# ACNode.net
KiCad netlist of a schematic drawn in EAGLE
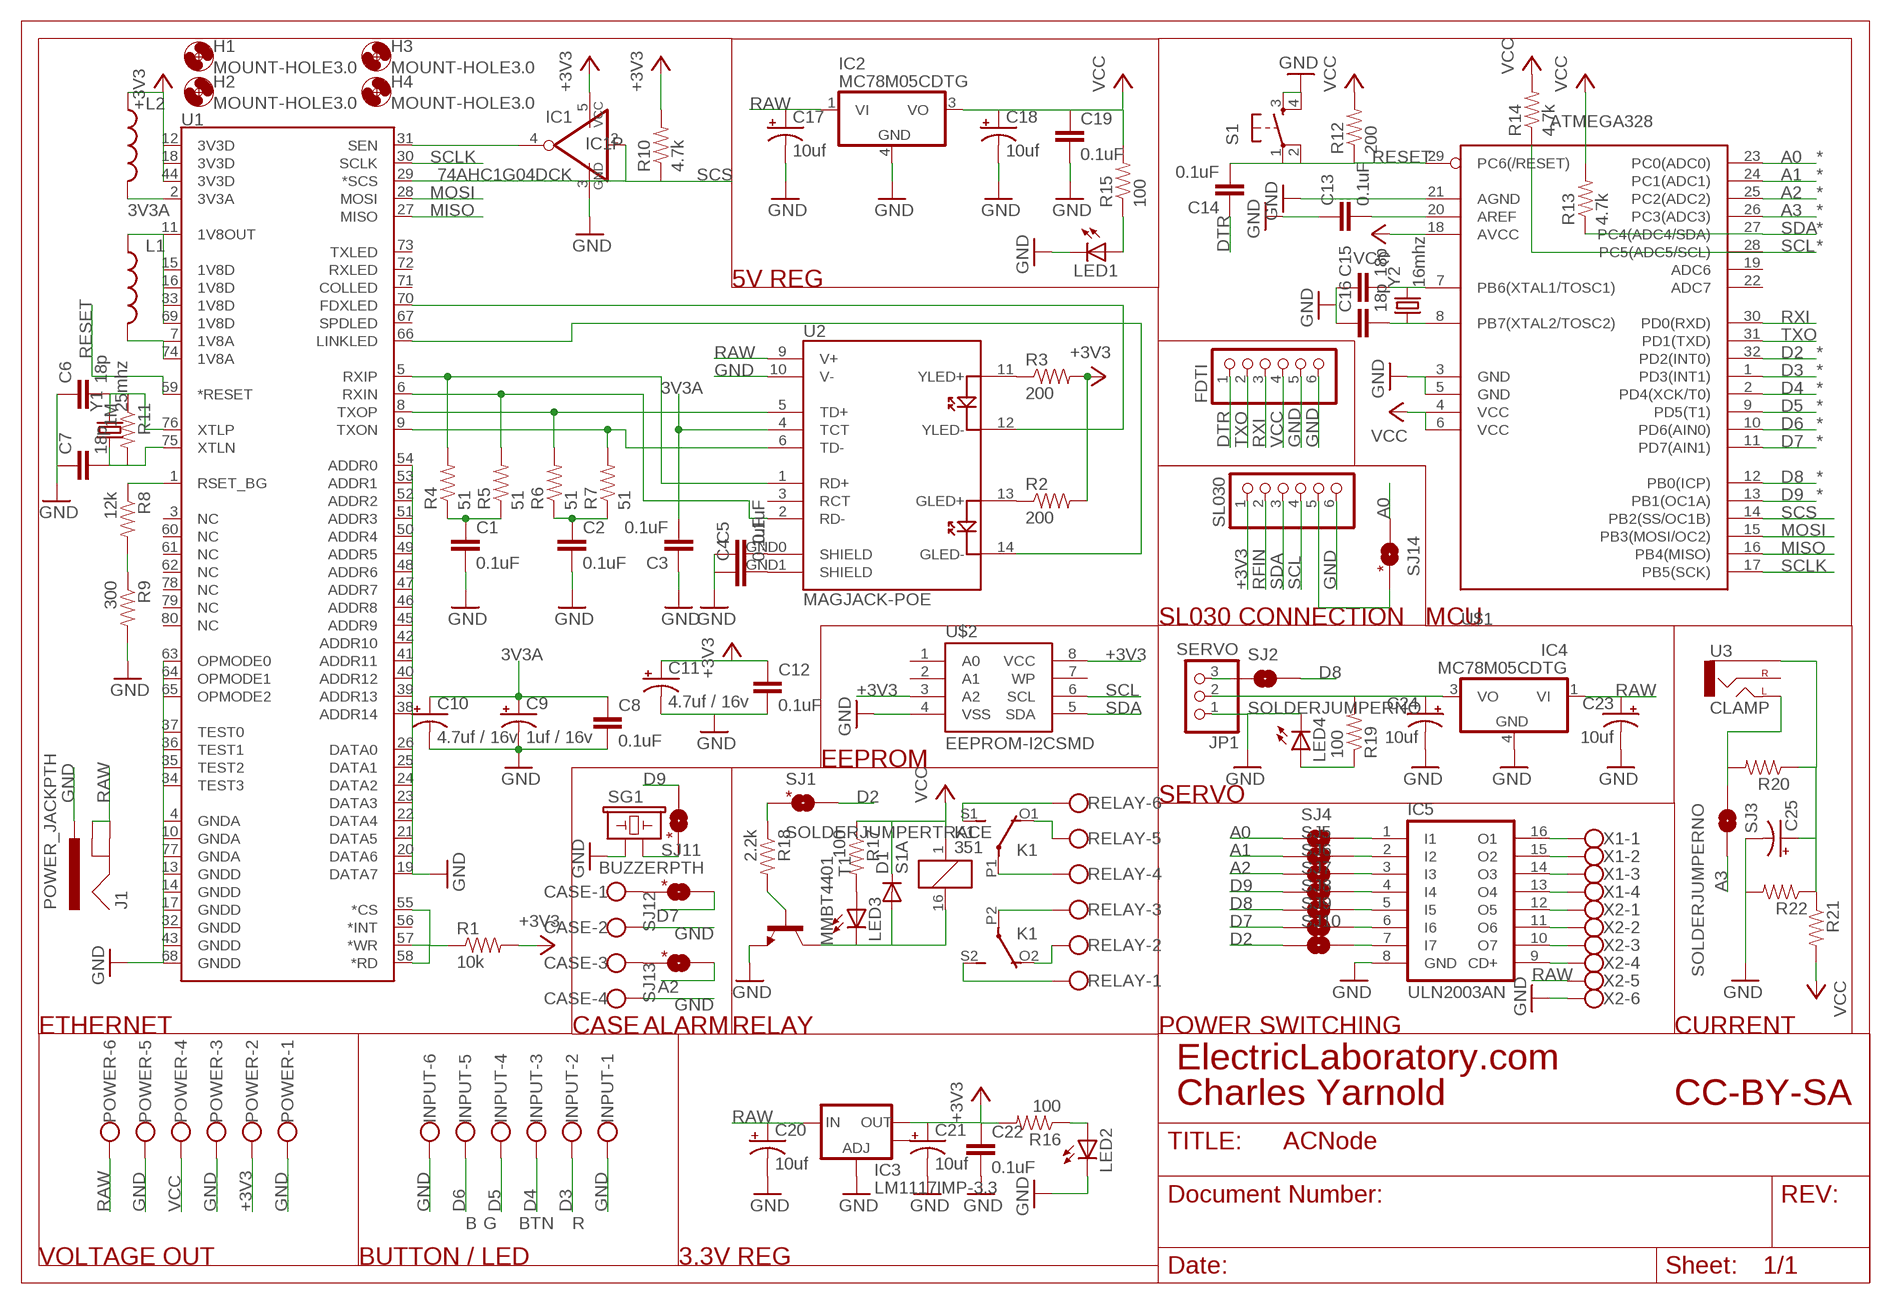
[diagram p0: schematic, sheet 1]

(export (version "E")
  (design (tool "Eeschema 10.0.6"))
  (components
    (comp (ref "C1")
      (value "0.1uF")
      (footprint "eagle-import:0603-CAP")
      (libsource (lib "eagle-import") (part "CAP0603-CAP"))
    )
    (comp (ref "C2")
      (value "0.1uF")
      (footprint "eagle-import:0603-CAP")
      (libsource (lib "eagle-import") (part "CAP0603-CAP"))
    )
    (comp (ref "C3")
      (value "0.1uF")
      (footprint "eagle-import:0603-CAP")
      (libsource (lib "eagle-import") (part "CAP0603-CAP"))
    )
    (comp (ref "C4")
      (value "0.1uF")
      (footprint "eagle-import:0603-CAP")
      (libsource (lib "eagle-import") (part "CAP0603-CAP"))
    )
    (comp (ref "C5")
      (value "0.1uF")
      (footprint "eagle-import:0603-CAP")
      (libsource (lib "eagle-import") (part "CAP0603-CAP"))
    )
    (comp (ref "C6")
      (value "18p")
      (footprint "eagle-import:0603-CAP")
      (libsource (lib "eagle-import") (part "CAP0603-CAP"))
    )
    (comp (ref "C7")
      (value "18p")
      (footprint "eagle-import:0603-CAP")
      (libsource (lib "eagle-import") (part "CAP0603-CAP"))
    )
    (comp (ref "C8")
      (value "0.1uF")
      (footprint "eagle-import:0603-CAP")
      (libsource (lib "eagle-import") (part "CAP0603-CAP"))
    )
    (comp (ref "C9")
      (value "1uf / 16v")
      (footprint "eagle-import:EIA3216")
      (libsource (lib "eagle-import") (part "CAP_POL1206"))
    )
    (comp (ref "C10")
      (value "4.7uf / 16v")
      (footprint "eagle-import:EIA3216")
      (libsource (lib "eagle-import") (part "CAP_POL1206"))
    )
    (comp (ref "C11")
      (value "4.7uf / 16v")
      (footprint "eagle-import:EIA3216")
      (libsource (lib "eagle-import") (part "CAP_POL1206"))
    )
    (comp (ref "C12")
      (value "0.1uF")
      (footprint "eagle-import:0603-CAP")
      (libsource (lib "eagle-import") (part "CAP0603-CAP"))
    )
    (comp (ref "C13")
      (value "0.1uF")
      (footprint "eagle-import:0603-CAP")
      (libsource (lib "eagle-import") (part "CAP0603-CAP"))
    )
    (comp (ref "C14")
      (value "0.1uF")
      (footprint "eagle-import:0603-CAP")
      (libsource (lib "eagle-import") (part "CAP0603-CAP"))
    )
    (comp (ref "C15")
      (value "18p")
      (footprint "eagle-import:0603-CAP")
      (libsource (lib "eagle-import") (part "CAP0603-CAP"))
    )
    (comp (ref "C16")
      (value "18p")
      (footprint "eagle-import:0603-CAP")
      (libsource (lib "eagle-import") (part "CAP0603-CAP"))
    )
    (comp (ref "C17")
      (value "10uf")
      (footprint "eagle-import:EIA3216")
      (libsource (lib "eagle-import") (part "CAP_POL1206"))
    )
    (comp (ref "C18")
      (value "10uf")
      (footprint "eagle-import:EIA3216")
      (libsource (lib "eagle-import") (part "CAP_POL1206"))
    )
    (comp (ref "C19")
      (value "0.1uF")
      (footprint "eagle-import:0603-CAP")
      (libsource (lib "eagle-import") (part "CAP0603-CAP"))
    )
    (comp (ref "C20")
      (value "10uf")
      (footprint "eagle-import:EIA3216")
      (libsource (lib "eagle-import") (part "CAP_POL1206"))
    )
    (comp (ref "C21")
      (value "10uf")
      (footprint "eagle-import:EIA3216")
      (libsource (lib "eagle-import") (part "CAP_POL1206"))
    )
    (comp (ref "C22")
      (value "0.1uF")
      (footprint "eagle-import:0603-CAP")
      (libsource (lib "eagle-import") (part "CAP0603-CAP"))
    )
    (comp (ref "C23")
      (value "10uf")
      (footprint "eagle-import:EIA3216")
      (libsource (lib "eagle-import") (part "CAP_POL1206"))
    )
    (comp (ref "C24")
      (value "10uf")
      (footprint "eagle-import:EIA3216")
      (libsource (lib "eagle-import") (part "CAP_POL1206"))
    )
    (comp (ref "C25")
      (value "CAP_POL1206")
      (footprint "eagle-import:EIA3216")
      (libsource (lib "eagle-import") (part "CAP_POL1206"))
    )
    (comp (ref "CASE")
      (value "W237-4")
      (footprint "eagle-import:W237-4")
      (libsource (lib "eagle-import") (part "W237-4"))
    )
    (comp (ref "D1")
      (value "S1A")
      (footprint "eagle-import:DO-214AC")
      (libsource (lib "eagle-import") (part "DIODE-DO-214AC"))
    )
    (comp (ref "FDTI")
      (value "PINHD-1X6")
      (footprint "eagle-import:1X06")
      (libsource (lib "eagle-import") (part "PINHD-1X6"))
    )
    (comp (ref "H1")
      (value "MOUNT-HOLE3.0")
      (footprint "eagle-import:3,0")
      (libsource (lib "eagle-import") (part "MOUNT-HOLE3.0"))
    )
    (comp (ref "H2")
      (value "MOUNT-HOLE3.0")
      (footprint "eagle-import:3,0")
      (libsource (lib "eagle-import") (part "MOUNT-HOLE3.0"))
    )
    (comp (ref "H3")
      (value "MOUNT-HOLE3.0")
      (footprint "eagle-import:3,0")
      (libsource (lib "eagle-import") (part "MOUNT-HOLE3.0"))
    )
    (comp (ref "H4")
      (value "MOUNT-HOLE3.0")
      (footprint "eagle-import:3,0")
      (libsource (lib "eagle-import") (part "MOUNT-HOLE3.0"))
    )
    (comp (ref "IC1")
      (value "74AHC1G04DCK")
      (footprint "eagle-import:SC70-5")
      (libsource (lib "eagle-import") (part "741G04DCKAHC"))
    )
    (comp (ref "IC2")
      (value "MC78M05CDTG")
      (footprint "eagle-import:DPACK_3")
      (libsource (lib "eagle-import") (part "MC78M05CDTG"))
    )
    (comp (ref "IC3")
      (value "LM1117IMP-3.3")
      (footprint "eagle-import:SOT223")
      (libsource (lib "eagle-import") (part "V_REG_LM1117SOT223"))
    )
    (comp (ref "IC4")
      (value "MC78M05CDTG")
      (footprint "eagle-import:DPACK_3")
      (libsource (lib "eagle-import") (part "MC78M05CDTG"))
    )
    (comp (ref "IC5")
      (value "ULN2003AN")
      (footprint "eagle-import:DIL16")
      (libsource (lib "eagle-import") (part "ULN2003AN"))
    )
    (comp (ref "INPUT")
      (value "W237-6")
      (footprint "eagle-import:W237-6")
      (libsource (lib "eagle-import") (part "W237-6"))
    )
    (comp (ref "J1")
      (value "POWER_JACKPTH")
      (footprint "eagle-import:POWER_JACK_PTH")
      (libsource (lib "eagle-import") (part "POWER_JACKPTH"))
    )
    (comp (ref "JP1")
      (value "SERVO")
      (footprint "eagle-import:1X03")
      (libsource (lib "eagle-import") (part "PINHD-1X3"))
    )
    (comp (ref "K1")
      (value "351")
      (footprint "eagle-import:351")
      (libsource (lib "eagle-import") (part "351"))
    )
    (comp (ref "L1")
      (value "INDUCTOR1206H*")
      (footprint "eagle-import:INDUCTOR-1206")
      (libsource (lib "eagle-import") (part "INDUCTORH1206"))
    )
    (comp (ref "L2")
      (value "INDUCTOR1206H*")
      (footprint "eagle-import:INDUCTOR-1206")
      (libsource (lib "eagle-import") (part "INDUCTORH1206"))
    )
    (comp (ref "LED1")
      (value "LED0603")
      (footprint "eagle-import:LED-0603")
      (libsource (lib "eagle-import") (part "LED0603"))
    )
    (comp (ref "LED2")
      (value "LED0603")
      (footprint "eagle-import:LED-0603")
      (libsource (lib "eagle-import") (part "LED0603"))
    )
    (comp (ref "LED3")
      (value "LED0603")
      (footprint "eagle-import:LED-0603")
      (libsource (lib "eagle-import") (part "LED0603"))
    )
    (comp (ref "LED4")
      (value "LED0603")
      (footprint "eagle-import:LED-0603")
      (libsource (lib "eagle-import") (part "LED0603"))
    )
    (comp (ref "POWER")
      (value "W237-6")
      (footprint "eagle-import:W237-6")
      (libsource (lib "eagle-import") (part "W237-6"))
    )
    (comp (ref "R1")
      (value "10k")
      (footprint "eagle-import:0603-RES")
      (libsource (lib "eagle-import") (part "RESISTOR0603-RES"))
    )
    (comp (ref "R2")
      (value "200")
      (footprint "eagle-import:0603-RES")
      (libsource (lib "eagle-import") (part "RESISTOR0603-RES"))
    )
    (comp (ref "R3")
      (value "200")
      (footprint "eagle-import:0603-RES")
      (libsource (lib "eagle-import") (part "RESISTOR0603-RES"))
    )
    (comp (ref "R4")
      (value "51")
      (footprint "eagle-import:0603-RES")
      (libsource (lib "eagle-import") (part "RESISTOR0603-RES"))
    )
    (comp (ref "R5")
      (value "51")
      (footprint "eagle-import:0603-RES")
      (libsource (lib "eagle-import") (part "RESISTOR0603-RES"))
    )
    (comp (ref "R6")
      (value "51")
      (footprint "eagle-import:0603-RES")
      (libsource (lib "eagle-import") (part "RESISTOR0603-RES"))
    )
    (comp (ref "R7")
      (value "51")
      (footprint "eagle-import:0603-RES")
      (libsource (lib "eagle-import") (part "RESISTOR0603-RES"))
    )
    (comp (ref "R8")
      (value "12k")
      (footprint "eagle-import:0603-RES")
      (libsource (lib "eagle-import") (part "RESISTOR0603-RES"))
    )
    (comp (ref "R9")
      (value "300")
      (footprint "eagle-import:0603-RES")
      (libsource (lib "eagle-import") (part "RESISTOR0603-RES"))
    )
    (comp (ref "R10")
      (value "4.7k")
      (footprint "eagle-import:0603-RES")
      (libsource (lib "eagle-import") (part "RESISTOR0603-RES"))
    )
    (comp (ref "R11")
      (value "1M")
      (footprint "eagle-import:0603-RES")
      (libsource (lib "eagle-import") (part "RESISTOR0603-RES"))
    )
    (comp (ref "R12")
      (value "200")
      (footprint "eagle-import:0603-RES")
      (libsource (lib "eagle-import") (part "RESISTOR0603-RES"))
    )
    (comp (ref "R13")
      (value "4.7k")
      (footprint "eagle-import:0603-RES")
      (libsource (lib "eagle-import") (part "RESISTOR0603-RES"))
    )
    (comp (ref "R14")
      (value "4.7k")
      (footprint "eagle-import:0603-RES")
      (libsource (lib "eagle-import") (part "RESISTOR0603-RES"))
    )
    (comp (ref "R15")
      (value "100")
      (footprint "eagle-import:0603-RES")
      (libsource (lib "eagle-import") (part "RESISTOR0603-RES"))
    )
    (comp (ref "R16")
      (value "100")
      (footprint "eagle-import:0603-RES")
      (libsource (lib "eagle-import") (part "RESISTOR0603-RES"))
    )
    (comp (ref "R17")
      (value "100")
      (footprint "eagle-import:0603-RES")
      (libsource (lib "eagle-import") (part "RESISTOR0603-RES"))
    )
    (comp (ref "R18")
      (value "2.2k")
      (footprint "eagle-import:0603-RES")
      (libsource (lib "eagle-import") (part "RESISTOR0603-RES"))
    )
    (comp (ref "R19")
      (value "100")
      (footprint "eagle-import:0603-RES")
      (libsource (lib "eagle-import") (part "RESISTOR0603-RES"))
    )
    (comp (ref "R20")
      (value "RESISTOR0603-RES")
      (footprint "eagle-import:0603-RES")
      (libsource (lib "eagle-import") (part "RESISTOR0603-RES"))
    )
    (comp (ref "R21")
      (value "RESISTOR0603-RES")
      (footprint "eagle-import:0603-RES")
      (libsource (lib "eagle-import") (part "RESISTOR0603-RES"))
    )
    (comp (ref "R22")
      (value "RESISTOR0603-RES")
      (footprint "eagle-import:0603-RES")
      (libsource (lib "eagle-import") (part "RESISTOR0603-RES"))
    )
    (comp (ref "RELAY")
      (value "W237-6")
      (footprint "eagle-import:W237-6")
      (libsource (lib "eagle-import") (part "W237-6"))
    )
    (comp (ref "S1")
      (value "TAC_SWITCHSMD")
      (footprint "eagle-import:TACTILE_SWITCH_SMD")
      (libsource (lib "eagle-import") (part "TAC_SWITCHSMD"))
    )
    (comp (ref "SG1")
      (value "BUZZERPTH")
      (footprint "eagle-import:BUZZER-12MM")
      (libsource (lib "eagle-import") (part "BUZZERPTH"))
    )
    (comp (ref "SJ1")
      (value "SOLDERJUMPERTRACE")
      (footprint "eagle-import:SJ_2S-TRACE")
      (libsource (lib "eagle-import") (part "SOLDERJUMPERTRACE"))
    )
    (comp (ref "SJ2")
      (value "SOLDERJUMPERNO")
      (footprint "eagle-import:SJ_2S-NO")
      (libsource (lib "eagle-import") (part "SOLDERJUMPERNO"))
    )
    (comp (ref "SJ3")
      (value "SOLDERJUMPERNO")
      (footprint "eagle-import:SJ_2S-NO")
      (libsource (lib "eagle-import") (part "SOLDERJUMPERNO"))
    )
    (comp (ref "SJ4")
      (value "SOLDERJUMPERNO")
      (footprint "eagle-import:SJ_2S-NO")
      (libsource (lib "eagle-import") (part "SOLDERJUMPERNO"))
    )
    (comp (ref "SJ5")
      (value "SOLDERJUMPERNO")
      (footprint "eagle-import:SJ_2S-NO")
      (libsource (lib "eagle-import") (part "SOLDERJUMPERNO"))
    )
    (comp (ref "SJ6")
      (value "SOLDERJUMPERNO")
      (footprint "eagle-import:SJ_2S-NO")
      (libsource (lib "eagle-import") (part "SOLDERJUMPERNO"))
    )
    (comp (ref "SJ7")
      (value "SOLDERJUMPERNO")
      (footprint "eagle-import:SJ_2S-NO")
      (libsource (lib "eagle-import") (part "SOLDERJUMPERNO"))
    )
    (comp (ref "SJ8")
      (value "SOLDERJUMPERNO")
      (footprint "eagle-import:SJ_2S-NO")
      (libsource (lib "eagle-import") (part "SOLDERJUMPERNO"))
    )
    (comp (ref "SJ9")
      (value "SOLDERJUMPERNO")
      (footprint "eagle-import:SJ_2S-NO")
      (libsource (lib "eagle-import") (part "SOLDERJUMPERNO"))
    )
    (comp (ref "SJ10")
      (value "SOLDERJUMPERNO")
      (footprint "eagle-import:SJ_2S-NO")
      (libsource (lib "eagle-import") (part "SOLDERJUMPERNO"))
    )
    (comp (ref "SJ11")
      (value "SOLDERJUMPERTRACE")
      (footprint "eagle-import:SJ_2S-TRACE")
      (libsource (lib "eagle-import") (part "SOLDERJUMPERTRACE"))
    )
    (comp (ref "SJ12")
      (value "SOLDERJUMPERTRACE")
      (footprint "eagle-import:SJ_2S-TRACE")
      (libsource (lib "eagle-import") (part "SOLDERJUMPERTRACE"))
    )
    (comp (ref "SJ13")
      (value "SOLDERJUMPERTRACE")
      (footprint "eagle-import:SJ_2S-TRACE")
      (libsource (lib "eagle-import") (part "SOLDERJUMPERTRACE"))
    )
    (comp (ref "SJ14")
      (value "SOLDERJUMPERTRACE")
      (footprint "eagle-import:SJ_2S-TRACE")
      (libsource (lib "eagle-import") (part "SOLDERJUMPERTRACE"))
    )
    (comp (ref "SL030")
      (value "PINHD-1X6")
      (footprint "eagle-import:1X06")
      (libsource (lib "eagle-import") (part "PINHD-1X6"))
    )
    (comp (ref "T1")
      (value "MMBT4401")
      (footprint "eagle-import:SOT23-BEC")
      (libsource (lib "eagle-import") (part "-NPN-SOT23-BECMMBT4401LT1"))
    )
    (comp (ref "U$1")
      (value "ATMEGA328")
      (footprint "eagle-import:TQFP32-08")
      (libsource (lib "eagle-import") (part "AVR-MEGA8-AI"))
    )
    (comp (ref "U$2")
      (value "EEPROM-I2CSMD")
      (footprint "eagle-import:SO08")
      (libsource (lib "eagle-import") (part "EEPROM-I2CSMD"))
    )
    (comp (ref "U1")
      (value "W5100")
      (footprint "eagle-import:LQFP-80")
      (libsource (lib "eagle-import") (part "W5100"))
    )
    (comp (ref "U2")
      (value "MAGJACK-POE")
      (footprint "eagle-import:MAGJACK-POE")
      (libsource (lib "eagle-import") (part "MAGJACK-POE"))
    )
    (comp (ref "U3")
      (value "CLAMP")
      (footprint "eagle-import:AUDIO-JACK")
      (libsource (lib "eagle-import") (part "AUDIO-JACKPTH"))
    )
    (comp (ref "X1")
      (value "W237-4")
      (footprint "eagle-import:W237-4")
      (libsource (lib "eagle-import") (part "W237-4"))
    )
    (comp (ref "X2")
      (value "W237-6")
      (footprint "eagle-import:W237-6")
      (libsource (lib "eagle-import") (part "W237-6"))
    )
    (comp (ref "Y1")
      (value "25mhz")
      (footprint "eagle-import:HC49UP")
      (libsource (lib "eagle-import") (part "CRYSTALSMD"))
    )
    (comp (ref "Y2")
      (value "16mhz")
      (footprint "eagle-import:HC49UP")
      (libsource (lib "eagle-import") (part "CRYSTALSMD"))
    )
  )
  (nets
    (net (code "1") (name "+3V3") (class "Default")
      (node (ref "C11") (pin "A") (pinfunction "+_A") (pintype "passive"))
      (node (ref "C12") (pin "1") (pinfunction "1_1") (pintype "passive"))
      (node (ref "C21") (pin "A") (pinfunction "+_A") (pintype "passive"))
      (node (ref "C22") (pin "1") (pinfunction "1_1") (pintype "passive"))
      (node (ref "IC1") (pin "5") (pinfunction "VCC_5") (pintype "power_in"))
      (node (ref "IC3") (pin "2") (pinfunction "OUT_2") (pintype "output"))
      (node (ref "L2") (pin "P$1") (pinfunction "1_P$1") (pintype "passive"))
      (node (ref "POWER") (pin "2") (pinfunction "KL_2") (pintype "passive"))
      (node (ref "R1") (pin "2") (pinfunction "2_2") (pintype "passive"))
      (node (ref "R10") (pin "2") (pinfunction "2_2") (pintype "passive"))
      (node (ref "R16") (pin "2") (pinfunction "2_2") (pintype "passive"))
      (node (ref "R2") (pin "2") (pinfunction "2_2") (pintype "passive"))
      (node (ref "R3") (pin "2") (pinfunction "2_2") (pintype "passive"))
      (node (ref "SL030") (pin "1") (pinfunction "1_1") (pintype "passive"))
      (node (ref "U$2") (pin "3") (pinfunction "A2_3") (pintype "bidirectional"))
      (node (ref "U$2") (pin "8") (pinfunction "VCC_8") (pintype "power_in"))
      (node (ref "U1") (pin "12") (pinfunction "3V3D_12") (pintype "bidirectional"))
      (node (ref "U1") (pin "18") (pinfunction "3V3D_18") (pintype "bidirectional"))
      (node (ref "U1") (pin "44") (pinfunction "3V3D_44") (pintype "bidirectional"))
    )
    (net (code "2") (name "/3V3A") (class "Default")
      (node (ref "C10") (pin "A") (pinfunction "+_A") (pintype "passive"))
      (node (ref "C3") (pin "2") (pinfunction "2_2") (pintype "passive"))
      (node (ref "C8") (pin "1") (pinfunction "1_1") (pintype "passive"))
      (node (ref "C9") (pin "A") (pinfunction "+_A") (pintype "passive"))
      (node (ref "L2") (pin "P$2") (pinfunction "2_P$2") (pintype "passive"))
      (node (ref "U1") (pin "2") (pinfunction "3V3A_2") (pintype "bidirectional"))
      (node (ref "U2") (pin "4") (pinfunction "TCT_4") (pintype "bidirectional"))
    )
    (net (code "3") (name "/A0") (class "Default")
      (node (ref "SJ14") (pin "1") (pinfunction "1_1") (pintype "passive"))
      (node (ref "SJ4") (pin "1") (pinfunction "1_1") (pintype "passive"))
      (node (ref "U$1") (pin "23") (pinfunction "PC0(ADC0)_23") (pintype "bidirectional"))
    )
    (net (code "4") (name "/A1") (class "Default")
      (node (ref "SJ5") (pin "1") (pinfunction "1_1") (pintype "passive"))
      (node (ref "U$1") (pin "24") (pinfunction "PC1(ADC1)_24") (pintype "bidirectional"))
    )
    (net (code "5") (name "/A2") (class "Default")
      (node (ref "SJ13") (pin "2") (pinfunction "2_2") (pintype "passive"))
      (node (ref "SJ6") (pin "1") (pinfunction "1_1") (pintype "passive"))
      (node (ref "U$1") (pin "25") (pinfunction "PC2(ADC2)_25") (pintype "bidirectional"))
    )
    (net (code "6") (name "/A3") (class "Default")
      (node (ref "SJ3") (pin "2") (pinfunction "2_2") (pintype "passive"))
      (node (ref "U$1") (pin "26") (pinfunction "PC3(ADC3)_26") (pintype "bidirectional"))
    )
    (net (code "7") (name "/D2") (class "Default")
      (node (ref "SJ1") (pin "2") (pinfunction "2_2") (pintype "passive"))
      (node (ref "SJ10") (pin "1") (pinfunction "1_1") (pintype "passive"))
      (node (ref "U$1") (pin "32") (pinfunction "PD2(INT0)_32") (pintype "bidirectional"))
    )
    (net (code "8") (name "/D3") (class "Default")
      (node (ref "INPUT") (pin "2") (pinfunction "KL_2") (pintype "passive"))
      (node (ref "U$1") (pin "1") (pinfunction "PD3(INT1)_1") (pintype "bidirectional"))
    )
    (net (code "9") (name "/D4") (class "Default")
      (node (ref "INPUT") (pin "3") (pinfunction "KL_3") (pintype "passive"))
      (node (ref "U$1") (pin "2") (pinfunction "PD4(XCK/T0)_2") (pintype "bidirectional"))
    )
    (net (code "10") (name "/D5") (class "Default")
      (node (ref "INPUT") (pin "4") (pinfunction "KL_4") (pintype "passive"))
      (node (ref "U$1") (pin "9") (pinfunction "PD5(T1)_9") (pintype "bidirectional"))
    )
    (net (code "11") (name "/D6") (class "Default")
      (node (ref "INPUT") (pin "5") (pinfunction "KL_5") (pintype "passive"))
      (node (ref "U$1") (pin "10") (pinfunction "PD6(AIN0)_10") (pintype "bidirectional"))
    )
    (net (code "12") (name "/D7") (class "Default")
      (node (ref "SJ12") (pin "2") (pinfunction "2_2") (pintype "passive"))
      (node (ref "SJ9") (pin "1") (pinfunction "1_1") (pintype "passive"))
      (node (ref "U$1") (pin "11") (pinfunction "PD7(AIN1)_11") (pintype "bidirectional"))
    )
    (net (code "13") (name "/D8") (class "Default")
      (node (ref "SJ2") (pin "2") (pinfunction "2_2") (pintype "passive"))
      (node (ref "SJ8") (pin "1") (pinfunction "1_1") (pintype "passive"))
      (node (ref "U$1") (pin "12") (pinfunction "PB0(ICP)_12") (pintype "bidirectional"))
    )
    (net (code "14") (name "/D9") (class "Default")
      (node (ref "SJ11") (pin "2") (pinfunction "2_2") (pintype "passive"))
      (node (ref "SJ7") (pin "1") (pinfunction "1_1") (pintype "passive"))
      (node (ref "U$1") (pin "13") (pinfunction "PB1(OC1A)_13") (pintype "bidirectional"))
    )
    (net (code "15") (name "/DTR") (class "Default")
      (node (ref "C14") (pin "1") (pinfunction "1_1") (pintype "passive"))
      (node (ref "FDTI") (pin "1") (pinfunction "1_1") (pintype "passive"))
    )
    (net (code "16") (name "/MISO") (class "Default")
      (node (ref "U$1") (pin "16") (pinfunction "PB4(MISO)_16") (pintype "bidirectional"))
      (node (ref "U1") (pin "27") (pinfunction "MISO_27") (pintype "bidirectional"))
    )
    (net (code "17") (name "/MOSI") (class "Default")
      (node (ref "U$1") (pin "15") (pinfunction "PB3(MOSI/OC2)_15") (pintype "bidirectional"))
      (node (ref "U1") (pin "28") (pinfunction "MOSI_28") (pintype "bidirectional"))
    )
    (net (code "18") (name "/RAW") (class "Default")
      (node (ref "C17") (pin "A") (pinfunction "+_A") (pintype "passive"))
      (node (ref "C20") (pin "A") (pinfunction "+_A") (pintype "passive"))
      (node (ref "C23") (pin "A") (pinfunction "+_A") (pintype "passive"))
      (node (ref "IC2") (pin "1") (pinfunction "VI_1") (pintype "input"))
      (node (ref "IC3") (pin "3") (pinfunction "IN_3") (pintype "input"))
      (node (ref "IC4") (pin "1") (pinfunction "VI_1") (pintype "input"))
      (node (ref "J1") (pin "GND") (pinfunction "GND_GND") (pintype "bidirectional"))
      (node (ref "J1") (pin "GNDBREAK") (pinfunction "GNDBREAK_GNDBREAK") (pintype "bidirectional"))
      (node (ref "POWER") (pin "6") (pinfunction "KL_6") (pintype "passive"))
      (node (ref "U2") (pin "9") (pinfunction "V+_9") (pintype "bidirectional"))
      (node (ref "X2") (pin "5") (pinfunction "KL_5") (pintype "passive"))
    )
    (net (code "19") (name "/RESET") (class "Default")
      (node (ref "C14") (pin "2") (pinfunction "2_2") (pintype "passive"))
      (node (ref "R12") (pin "1") (pinfunction "1_1") (pintype "passive"))
      (node (ref "S1") (pin "1") (pinfunction "1_1") (pintype "passive"))
      (node (ref "S1") (pin "2") (pinfunction "2_2") (pintype "passive"))
      (node (ref "U$1") (pin "29") (pinfunction "PC6(/RESET)_29") (pintype "bidirectional"))
      (node (ref "U1") (pin "59") (pinfunction "*RESET_59") (pintype "bidirectional"))
    )
    (net (code "20") (name "/RFIN") (class "Default")
      (node (ref "SL030") (pin "2") (pinfunction "2_2") (pintype "passive"))
    )
    (net (code "21") (name "/RXI") (class "Default")
      (node (ref "FDTI") (pin "3") (pinfunction "3_3") (pintype "passive"))
      (node (ref "U$1") (pin "30") (pinfunction "PD0(RXD)_30") (pintype "bidirectional"))
    )
    (net (code "22") (name "/SCL") (class "Default")
      (node (ref "R14") (pin "1") (pinfunction "1_1") (pintype "passive"))
      (node (ref "SL030") (pin "4") (pinfunction "4_4") (pintype "passive"))
      (node (ref "U$1") (pin "28") (pinfunction "PC5(ADC5/SCL)_28") (pintype "bidirectional"))
      (node (ref "U$2") (pin "6") (pinfunction "SCL_6") (pintype "bidirectional"))
    )
    (net (code "23") (name "/SCLK") (class "Default")
      (node (ref "U$1") (pin "17") (pinfunction "PB5(SCK)_17") (pintype "bidirectional"))
      (node (ref "U1") (pin "30") (pinfunction "SCLK_30") (pintype "bidirectional"))
    )
    (net (code "24") (name "/SCS") (class "Default")
      (node (ref "IC1") (pin "2") (pinfunction "I_2") (pintype "input"))
      (node (ref "R10") (pin "1") (pinfunction "1_1") (pintype "passive"))
      (node (ref "U$1") (pin "14") (pinfunction "PB2(SS/OC1B)_14") (pintype "bidirectional"))
      (node (ref "U1") (pin "29") (pinfunction "*SCS_29") (pintype "bidirectional"))
    )
    (net (code "25") (name "/SDA") (class "Default")
      (node (ref "R13") (pin "1") (pinfunction "1_1") (pintype "passive"))
      (node (ref "SL030") (pin "3") (pinfunction "3_3") (pintype "passive"))
      (node (ref "U$1") (pin "27") (pinfunction "PC4(ADC4/SDA)_27") (pintype "bidirectional"))
      (node (ref "U$2") (pin "5") (pinfunction "SDA_5") (pintype "bidirectional"))
    )
    (net (code "26") (name "/TXO") (class "Default")
      (node (ref "FDTI") (pin "2") (pinfunction "2_2") (pintype "passive"))
      (node (ref "U$1") (pin "31") (pinfunction "PD1(TXD)_31") (pintype "bidirectional"))
    )
    (net (code "27") (name "GND") (class "Default")
      (node (ref "C1") (pin "2") (pinfunction "2_2") (pintype "passive"))
      (node (ref "C10") (pin "C") (pinfunction "-_C") (pintype "passive"))
      (node (ref "C11") (pin "C") (pinfunction "-_C") (pintype "passive"))
      (node (ref "C12") (pin "2") (pinfunction "2_2") (pintype "passive"))
      (node (ref "C13") (pin "1") (pinfunction "1_1") (pintype "passive"))
      (node (ref "C15") (pin "1") (pinfunction "1_1") (pintype "passive"))
      (node (ref "C16") (pin "1") (pinfunction "1_1") (pintype "passive"))
      (node (ref "C17") (pin "C") (pinfunction "-_C") (pintype "passive"))
      (node (ref "C18") (pin "C") (pinfunction "-_C") (pintype "passive"))
      (node (ref "C19") (pin "2") (pinfunction "2_2") (pintype "passive"))
      (node (ref "C2") (pin "2") (pinfunction "2_2") (pintype "passive"))
      (node (ref "C20") (pin "C") (pinfunction "-_C") (pintype "passive"))
      (node (ref "C21") (pin "C") (pinfunction "-_C") (pintype "passive"))
      (node (ref "C22") (pin "2") (pinfunction "2_2") (pintype "passive"))
      (node (ref "C23") (pin "C") (pinfunction "-_C") (pintype "passive"))
      (node (ref "C24") (pin "C") (pinfunction "-_C") (pintype "passive"))
      (node (ref "C25") (pin "C") (pinfunction "-_C") (pintype "passive"))
      (node (ref "C3") (pin "1") (pinfunction "1_1") (pintype "passive"))
      (node (ref "C4") (pin "1") (pinfunction "1_1") (pintype "passive"))
      (node (ref "C5") (pin "1") (pinfunction "1_1") (pintype "passive"))
      (node (ref "C6") (pin "1") (pinfunction "1_1") (pintype "passive"))
      (node (ref "C7") (pin "1") (pinfunction "1_1") (pintype "passive"))
      (node (ref "C8") (pin "2") (pinfunction "2_2") (pintype "passive"))
      (node (ref "C9") (pin "C") (pinfunction "-_C") (pintype "passive"))
      (node (ref "CASE") (pin "2") (pinfunction "KL_2") (pintype "passive"))
      (node (ref "CASE") (pin "4") (pinfunction "KL_4") (pintype "passive"))
      (node (ref "FDTI") (pin "5") (pinfunction "5_5") (pintype "passive"))
      (node (ref "FDTI") (pin "6") (pinfunction "6_6") (pintype "passive"))
      (node (ref "IC1") (pin "3") (pinfunction "GND_3") (pintype "power_in"))
      (node (ref "IC2") (pin "4") (pinfunction "GND_4") (pintype "passive"))
      (node (ref "IC3") (pin "1") (pinfunction "ADJ_1") (pintype "input"))
      (node (ref "IC4") (pin "4") (pinfunction "GND_4") (pintype "passive"))
      (node (ref "IC5") (pin "8") (pinfunction "GND_8") (pintype "power_in"))
      (node (ref "INPUT") (pin "1") (pinfunction "KL_1") (pintype "passive"))
      (node (ref "INPUT") (pin "6") (pinfunction "KL_6") (pintype "passive"))
      (node (ref "J1") (pin "PWR") (pinfunction "PWR_PWR") (pintype "bidirectional"))
      (node (ref "JP1") (pin "1") (pinfunction "1_1") (pintype "passive"))
      (node (ref "LED1") (pin "C") (pinfunction "C_C") (pintype "passive"))
      (node (ref "LED2") (pin "C") (pinfunction "C_C") (pintype "passive"))
      (node (ref "LED4") (pin "C") (pinfunction "C_C") (pintype "passive"))
      (node (ref "POWER") (pin "1") (pinfunction "KL_1") (pintype "passive"))
      (node (ref "POWER") (pin "3") (pinfunction "KL_3") (pintype "passive"))
      (node (ref "POWER") (pin "5") (pinfunction "KL_5") (pintype "passive"))
      (node (ref "R22") (pin "2") (pinfunction "2_2") (pintype "passive"))
      (node (ref "R9") (pin "2") (pinfunction "2_2") (pintype "passive"))
      (node (ref "S1") (pin "3") (pinfunction "3_3") (pintype "passive"))
      (node (ref "S1") (pin "4") (pinfunction "4_4") (pintype "passive"))
      (node (ref "SG1") (pin "+") (pinfunction "1_+") (pintype "passive"))
      (node (ref "SL030") (pin "6") (pinfunction "6_6") (pintype "passive"))
      (node (ref "T1") (pin "E") (pinfunction "E_E") (pintype "passive"))
      (node (ref "U$1") (pin "21") (pinfunction "AGND_21") (pintype "bidirectional"))
      (node (ref "U$1") (pin "3") (pinfunction "GND_3") (pintype "bidirectional"))
      (node (ref "U$1") (pin "5") (pinfunction "GND_5") (pintype "bidirectional"))
      (node (ref "U$2") (pin "4") (pinfunction "VSS_4") (pintype "power_in"))
      (node (ref "U1") (pin "10") (pinfunction "GNDA_10") (pintype "bidirectional"))
      (node (ref "U1") (pin "13") (pinfunction "GNDD_13") (pintype "bidirectional"))
      (node (ref "U1") (pin "14") (pinfunction "GNDD_14") (pintype "bidirectional"))
      (node (ref "U1") (pin "17") (pinfunction "GNDD_17") (pintype "bidirectional"))
      (node (ref "U1") (pin "19") (pinfunction "DATA7_19") (pintype "bidirectional"))
      (node (ref "U1") (pin "20") (pinfunction "DATA6_20") (pintype "bidirectional"))
      (node (ref "U1") (pin "21") (pinfunction "DATA5_21") (pintype "bidirectional"))
      (node (ref "U1") (pin "22") (pinfunction "DATA4_22") (pintype "bidirectional"))
      (node (ref "U1") (pin "23") (pinfunction "DATA3_23") (pintype "bidirectional"))
      (node (ref "U1") (pin "24") (pinfunction "DATA2_24") (pintype "bidirectional"))
      (node (ref "U1") (pin "25") (pinfunction "DATA1_25") (pintype "bidirectional"))
      (node (ref "U1") (pin "26") (pinfunction "DATA0_26") (pintype "bidirectional"))
      (node (ref "U1") (pin "32") (pinfunction "GNDD_32") (pintype "bidirectional"))
      (node (ref "U1") (pin "34") (pinfunction "TEST3_34") (pintype "bidirectional"))
      (node (ref "U1") (pin "35") (pinfunction "TEST2_35") (pintype "bidirectional"))
      (node (ref "U1") (pin "36") (pinfunction "TEST1_36") (pintype "bidirectional"))
      (node (ref "U1") (pin "37") (pinfunction "TEST0_37") (pintype "bidirectional"))
      (node (ref "U1") (pin "38") (pinfunction "ADDR14_38") (pintype "bidirectional"))
      (node (ref "U1") (pin "39") (pinfunction "ADDR13_39") (pintype "bidirectional"))
      (node (ref "U1") (pin "4") (pinfunction "GNDA_4") (pintype "bidirectional"))
      (node (ref "U1") (pin "40") (pinfunction "ADDR12_40") (pintype "bidirectional"))
      (node (ref "U1") (pin "41") (pinfunction "ADDR11_41") (pintype "bidirectional"))
      (node (ref "U1") (pin "42") (pinfunction "ADDR10_42") (pintype "bidirectional"))
      (node (ref "U1") (pin "43") (pinfunction "GNDD_43") (pintype "bidirectional"))
      (node (ref "U1") (pin "45") (pinfunction "ADDR9_45") (pintype "bidirectional"))
      (node (ref "U1") (pin "46") (pinfunction "ADDR8_46") (pintype "bidirectional"))
      (node (ref "U1") (pin "47") (pinfunction "ADDR7_47") (pintype "bidirectional"))
      (node (ref "U1") (pin "48") (pinfunction "ADDR6_48") (pintype "bidirectional"))
      (node (ref "U1") (pin "49") (pinfunction "ADDR5_49") (pintype "bidirectional"))
      (node (ref "U1") (pin "50") (pinfunction "ADDR4_50") (pintype "bidirectional"))
      (node (ref "U1") (pin "51") (pinfunction "ADDR3_51") (pintype "bidirectional"))
      (node (ref "U1") (pin "52") (pinfunction "ADDR2_52") (pintype "bidirectional"))
      (node (ref "U1") (pin "53") (pinfunction "ADDR1_53") (pintype "bidirectional"))
      (node (ref "U1") (pin "54") (pinfunction "ADDR0_54") (pintype "bidirectional"))
      (node (ref "U1") (pin "63") (pinfunction "OPMODE0_63") (pintype "bidirectional"))
      (node (ref "U1") (pin "64") (pinfunction "OPMODE1_64") (pintype "bidirectional"))
      (node (ref "U1") (pin "65") (pinfunction "OPMODE2_65") (pintype "bidirectional"))
      (node (ref "U1") (pin "68") (pinfunction "GNDD_68") (pintype "bidirectional"))
      (node (ref "U1") (pin "77") (pinfunction "GNDA_77") (pintype "bidirectional"))
      (node (ref "U2") (pin "10") (pinfunction "V-_10") (pintype "bidirectional"))
      (node (ref "X2") (pin "6") (pinfunction "KL_6") (pintype "passive"))
    )
    (net (code "28") (name "Net-(C1-Pad1)") (class "Default")
      (node (ref "C1") (pin "1") (pinfunction "1_1") (pintype "passive"))
      (node (ref "R4") (pin "1") (pinfunction "1_1") (pintype "passive"))
      (node (ref "R5") (pin "1") (pinfunction "1_1") (pintype "passive"))
    )
    (net (code "29") (name "Net-(C2-Pad1)") (class "Default")
      (node (ref "C2") (pin "1") (pinfunction "1_1") (pintype "passive"))
      (node (ref "R6") (pin "1") (pinfunction "1_1") (pintype "passive"))
      (node (ref "R7") (pin "1") (pinfunction "1_1") (pintype "passive"))
    )
    (net (code "30") (name "Net-(C4-Pad2)") (class "Default")
      (node (ref "C4") (pin "2") (pinfunction "2_2") (pintype "passive"))
      (node (ref "U2") (pin "GND1") (pinfunction "SHIELD_GND1") (pintype "bidirectional"))
    )
    (net (code "31") (name "Net-(C5-Pad2)") (class "Default")
      (node (ref "C5") (pin "2") (pinfunction "2_2") (pintype "passive"))
      (node (ref "U2") (pin "GND0") (pinfunction "SHIELD_GND0") (pintype "bidirectional"))
    )
    (net (code "32") (name "Net-(C24-+)") (class "Default")
      (node (ref "C24") (pin "A") (pinfunction "+_A") (pintype "passive"))
      (node (ref "IC4") (pin "3") (pinfunction "VO_3") (pintype "passive"))
      (node (ref "JP1") (pin "2") (pinfunction "2_2") (pintype "passive"))
      (node (ref "R19") (pin "2") (pinfunction "2_2") (pintype "passive"))
    )
    (net (code "33") (name "Net-(C25-+)") (class "Default")
      (node (ref "C25") (pin "A") (pinfunction "+_A") (pintype "passive"))
      (node (ref "R20") (pin "1") (pinfunction "1_1") (pintype "passive"))
      (node (ref "R21") (pin "1") (pinfunction "1_1") (pintype "passive"))
      (node (ref "R22") (pin "1") (pinfunction "1_1") (pintype "passive"))
      (node (ref "U3") (pin "SLEEVE") (pinfunction "SLEEVE_SLEEVE") (pintype "bidirectional"))
    )
    (net (code "34") (name "Net-(CASEA-KL)") (class "Default")
      (node (ref "CASE") (pin "1") (pinfunction "KL_1") (pintype "passive"))
      (node (ref "SJ12") (pin "1") (pinfunction "1_1") (pintype "passive"))
    )
    (net (code "35") (name "Net-(CASEC-KL)") (class "Default")
      (node (ref "CASE") (pin "3") (pinfunction "KL_3") (pintype "passive"))
      (node (ref "SJ13") (pin "1") (pinfunction "1_1") (pintype "passive"))
    )
    (net (code "36") (name "Net-(IC1A-O)") (class "Default")
      (node (ref "IC1") (pin "4") (pinfunction "O_4") (pintype "output"))
      (node (ref "U1") (pin "31") (pinfunction "SEN_31") (pintype "bidirectional"))
    )
    (net (code "37") (name "Net-(IC5-CD+)") (class "Default")
      (node (ref "IC5") (pin "9") (pinfunction "CD+_9") (pintype "passive"))
      (node (ref "X2") (pin "4") (pinfunction "KL_4") (pintype "passive"))
    )
    (net (code "38") (name "Net-(IC5-I1)") (class "Default")
      (node (ref "IC5") (pin "1") (pinfunction "I1_1") (pintype "input"))
      (node (ref "SJ4") (pin "2") (pinfunction "2_2") (pintype "passive"))
    )
    (net (code "39") (name "Net-(IC5-I2)") (class "Default")
      (node (ref "IC5") (pin "2") (pinfunction "I2_2") (pintype "input"))
      (node (ref "SJ5") (pin "2") (pinfunction "2_2") (pintype "passive"))
    )
    (net (code "40") (name "Net-(IC5-I3)") (class "Default")
      (node (ref "IC5") (pin "3") (pinfunction "I3_3") (pintype "input"))
      (node (ref "SJ6") (pin "2") (pinfunction "2_2") (pintype "passive"))
    )
    (net (code "41") (name "Net-(IC5-I4)") (class "Default")
      (node (ref "IC5") (pin "4") (pinfunction "I4_4") (pintype "input"))
      (node (ref "SJ7") (pin "2") (pinfunction "2_2") (pintype "passive"))
    )
    (net (code "42") (name "Net-(IC5-I5)") (class "Default")
      (node (ref "IC5") (pin "5") (pinfunction "I5_5") (pintype "input"))
      (node (ref "SJ8") (pin "2") (pinfunction "2_2") (pintype "passive"))
    )
    (net (code "43") (name "Net-(IC5-I6)") (class "Default")
      (node (ref "IC5") (pin "6") (pinfunction "I6_6") (pintype "input"))
      (node (ref "SJ9") (pin "2") (pinfunction "2_2") (pintype "passive"))
    )
    (net (code "44") (name "Net-(IC5-I7)") (class "Default")
      (node (ref "IC5") (pin "7") (pinfunction "I7_7") (pintype "input"))
      (node (ref "SJ10") (pin "2") (pinfunction "2_2") (pintype "passive"))
    )
    (net (code "45") (name "Net-(IC5-O1)") (class "Default")
      (node (ref "IC5") (pin "16") (pinfunction "O1_16") (pintype "open_collector"))
      (node (ref "X1") (pin "1") (pinfunction "KL_1") (pintype "passive"))
    )
    (net (code "46") (name "Net-(IC5-O2)") (class "Default")
      (node (ref "IC5") (pin "15") (pinfunction "O2_15") (pintype "open_collector"))
      (node (ref "X1") (pin "2") (pinfunction "KL_2") (pintype "passive"))
    )
    (net (code "47") (name "Net-(IC5-O3)") (class "Default")
      (node (ref "IC5") (pin "14") (pinfunction "O3_14") (pintype "open_collector"))
      (node (ref "X1") (pin "3") (pinfunction "KL_3") (pintype "passive"))
    )
    (net (code "48") (name "Net-(IC5-O4)") (class "Default")
      (node (ref "IC5") (pin "13") (pinfunction "O4_13") (pintype "open_collector"))
      (node (ref "X1") (pin "4") (pinfunction "KL_4") (pintype "passive"))
    )
    (net (code "49") (name "Net-(IC5-O5)") (class "Default")
      (node (ref "IC5") (pin "12") (pinfunction "O5_12") (pintype "open_collector"))
      (node (ref "X2") (pin "1") (pinfunction "KL_1") (pintype "passive"))
    )
    (net (code "50") (name "Net-(IC5-O6)") (class "Default")
      (node (ref "IC5") (pin "11") (pinfunction "O6_11") (pintype "open_collector"))
      (node (ref "X2") (pin "2") (pinfunction "KL_2") (pintype "passive"))
    )
    (net (code "51") (name "Net-(IC5-O7)") (class "Default")
      (node (ref "IC5") (pin "10") (pinfunction "O7_10") (pintype "open_collector"))
      (node (ref "X2") (pin "3") (pinfunction "KL_3") (pintype "passive"))
    )
    (net (code "52") (name "Net-(JP1-Pad3)") (class "Default")
      (node (ref "JP1") (pin "3") (pinfunction "3_3") (pintype "passive"))
      (node (ref "SJ2") (pin "1") (pinfunction "1_1") (pintype "passive"))
    )
    (net (code "53") (name "Net-(K1A-2)") (class "Default")
      (node (ref "D1") (pin "A") (pinfunction "A_A") (pintype "passive"))
      (node (ref "K1") (pin "16") (pinfunction "2_16") (pintype "passive"))
      (node (ref "LED3") (pin "C") (pinfunction "C_C") (pintype "passive"))
      (node (ref "T1") (pin "C") (pinfunction "C_C") (pintype "passive"))
    )
    (net (code "54") (name "Net-(K1B-O)") (class "Default")
      (node (ref "K1") (pin "O1") (pinfunction "O_O1") (pintype "passive"))
      (node (ref "RELAY") (pin "5") (pinfunction "KL_5") (pintype "passive"))
    )
    (net (code "55") (name "Net-(K1B-P)") (class "Default")
      (node (ref "K1") (pin "P1") (pinfunction "P_P1") (pintype "passive"))
      (node (ref "RELAY") (pin "4") (pinfunction "KL_4") (pintype "passive"))
    )
    (net (code "56") (name "Net-(K1B-S)") (class "Default")
      (node (ref "K1") (pin "S1") (pinfunction "S_S1") (pintype "passive"))
      (node (ref "RELAY") (pin "6") (pinfunction "KL_6") (pintype "passive"))
    )
    (net (code "57") (name "Net-(K1C-O)") (class "Default")
      (node (ref "K1") (pin "O2") (pinfunction "O_O2") (pintype "passive"))
      (node (ref "RELAY") (pin "2") (pinfunction "KL_2") (pintype "passive"))
    )
    (net (code "58") (name "Net-(K1C-P)") (class "Default")
      (node (ref "K1") (pin "P2") (pinfunction "P_P2") (pintype "passive"))
      (node (ref "RELAY") (pin "3") (pinfunction "KL_3") (pintype "passive"))
    )
    (net (code "59") (name "Net-(K1C-S)") (class "Default")
      (node (ref "K1") (pin "S2") (pinfunction "S_S2") (pintype "passive"))
      (node (ref "RELAY") (pin "1") (pinfunction "KL_1") (pintype "passive"))
    )
    (net (code "60") (name "Net-(L1-1)") (class "Default")
      (node (ref "L1") (pin "P$1") (pinfunction "1_P$1") (pintype "passive"))
      (node (ref "U1") (pin "11") (pinfunction "1V8OUT_11") (pintype "bidirectional"))
      (node (ref "U1") (pin "15") (pinfunction "1V8D_15") (pintype "bidirectional"))
      (node (ref "U1") (pin "16") (pinfunction "1V8D_16") (pintype "bidirectional"))
      (node (ref "U1") (pin "33") (pinfunction "1V8D_33") (pintype "bidirectional"))
      (node (ref "U1") (pin "69") (pinfunction "1V8D_69") (pintype "bidirectional"))
    )
    (net (code "61") (name "Net-(L1-2)") (class "Default")
      (node (ref "L1") (pin "P$2") (pinfunction "2_P$2") (pintype "passive"))
      (node (ref "U1") (pin "7") (pinfunction "1V8A_7") (pintype "bidirectional"))
      (node (ref "U1") (pin "74") (pinfunction "1V8A_74") (pintype "bidirectional"))
    )
    (net (code "62") (name "Net-(LED1-PadA)") (class "Default")
      (node (ref "LED1") (pin "A") (pinfunction "A_A") (pintype "passive"))
      (node (ref "R15") (pin "1") (pinfunction "1_1") (pintype "passive"))
    )
    (net (code "63") (name "Net-(LED2-PadA)") (class "Default")
      (node (ref "LED2") (pin "A") (pinfunction "A_A") (pintype "passive"))
      (node (ref "R16") (pin "1") (pinfunction "1_1") (pintype "passive"))
    )
    (net (code "64") (name "Net-(LED3-PadA)") (class "Default")
      (node (ref "LED3") (pin "A") (pinfunction "A_A") (pintype "passive"))
      (node (ref "R17") (pin "2") (pinfunction "2_2") (pintype "passive"))
    )
    (net (code "65") (name "Net-(LED4-PadA)") (class "Default")
      (node (ref "LED4") (pin "A") (pinfunction "A_A") (pintype "passive"))
      (node (ref "R19") (pin "1") (pinfunction "1_1") (pintype "passive"))
    )
    (net (code "66") (name "Net-(R8-Pad2)") (class "Default")
      (node (ref "R8") (pin "2") (pinfunction "2_2") (pintype "passive"))
      (node (ref "R9") (pin "1") (pinfunction "1_1") (pintype "passive"))
    )
    (net (code "67") (name "Net-(R18-Pad1)") (class "Default")
      (node (ref "R18") (pin "1") (pinfunction "1_1") (pintype "passive"))
      (node (ref "SJ1") (pin "1") (pinfunction "1_1") (pintype "passive"))
    )
    (net (code "68") (name "Net-(R18-Pad2)") (class "Default")
      (node (ref "R18") (pin "2") (pinfunction "2_2") (pintype "passive"))
      (node (ref "T1") (pin "B") (pinfunction "B_B") (pintype "passive"))
    )
    (net (code "69") (name "Net-(SG1-2)") (class "Default")
      (node (ref "SG1") (pin "-") (pinfunction "2_-") (pintype "passive"))
      (node (ref "SJ11") (pin "1") (pinfunction "1_1") (pintype "passive"))
    )
    (net (code "70") (name "Net-(SJ14-Pad2)") (class "Default")
      (node (ref "SJ14") (pin "2") (pinfunction "2_2") (pintype "passive"))
      (node (ref "SL030") (pin "5") (pinfunction "5_5") (pintype "passive"))
    )
    (net (code "71") (name "Net-(U$1-AREF)") (class "Default")
      (node (ref "C13") (pin "2") (pinfunction "2_2") (pintype "passive"))
      (node (ref "U$1") (pin "20") (pinfunction "AREF_20") (pintype "bidirectional"))
    )
    (net (code "72") (name "Net-(U$1-PB6(XTAL1{slash}TOSC1))") (class "Default")
      (node (ref "C15") (pin "2") (pinfunction "2_2") (pintype "passive"))
      (node (ref "U$1") (pin "7") (pinfunction "PB6(XTAL1/TOSC1)_7") (pintype "bidirectional"))
      (node (ref "Y2") (pin "2") (pinfunction "2_2") (pintype "passive"))
    )
    (net (code "73") (name "Net-(U$1-PB7(XTAL2{slash}TOSC2))") (class "Default")
      (node (ref "C16") (pin "2") (pinfunction "2_2") (pintype "passive"))
      (node (ref "U$1") (pin "8") (pinfunction "PB7(XTAL2/TOSC2)_8") (pintype "bidirectional"))
      (node (ref "Y2") (pin "1") (pinfunction "1_1") (pintype "passive"))
    )
    (net (code "74") (name "Net-(U1-*CS)") (class "Default")
      (node (ref "R1") (pin "1") (pinfunction "1_1") (pintype "passive"))
      (node (ref "U1") (pin "55") (pinfunction "*CS_55") (pintype "bidirectional"))
      (node (ref "U1") (pin "57") (pinfunction "*WR_57") (pintype "bidirectional"))
      (node (ref "U1") (pin "58") (pinfunction "*RD_58") (pintype "bidirectional"))
    )
    (net (code "75") (name "Net-(U1-FDXLED)") (class "Default")
      (node (ref "U1") (pin "70") (pinfunction "FDXLED_70") (pintype "bidirectional"))
      (node (ref "U2") (pin "12") (pinfunction "YLED-_12") (pintype "bidirectional"))
    )
    (net (code "76") (name "Net-(U1-LINKLED)") (class "Default")
      (node (ref "U1") (pin "66") (pinfunction "LINKLED_66") (pintype "bidirectional"))
      (node (ref "U2") (pin "14") (pinfunction "GLED-_14") (pintype "bidirectional"))
    )
    (net (code "77") (name "Net-(U1-RSET_BG)") (class "Default")
      (node (ref "R8") (pin "1") (pinfunction "1_1") (pintype "passive"))
      (node (ref "U1") (pin "1") (pinfunction "RSET_BG_1") (pintype "bidirectional"))
    )
    (net (code "78") (name "Net-(U1-RXIN)") (class "Default")
      (node (ref "R5") (pin "2") (pinfunction "2_2") (pintype "passive"))
      (node (ref "U1") (pin "6") (pinfunction "RXIN_6") (pintype "bidirectional"))
      (node (ref "U2") (pin "2") (pinfunction "RD-_2") (pintype "bidirectional"))
    )
    (net (code "79") (name "Net-(U1-RXIP)") (class "Default")
      (node (ref "R4") (pin "2") (pinfunction "2_2") (pintype "passive"))
      (node (ref "U1") (pin "5") (pinfunction "RXIP_5") (pintype "bidirectional"))
      (node (ref "U2") (pin "1") (pinfunction "RD+_1") (pintype "bidirectional"))
    )
    (net (code "80") (name "Net-(U1-TXON)") (class "Default")
      (node (ref "R7") (pin "2") (pinfunction "2_2") (pintype "passive"))
      (node (ref "U1") (pin "9") (pinfunction "TXON_9") (pintype "bidirectional"))
      (node (ref "U2") (pin "6") (pinfunction "TD-_6") (pintype "bidirectional"))
    )
    (net (code "81") (name "Net-(U1-TXOP)") (class "Default")
      (node (ref "R6") (pin "2") (pinfunction "2_2") (pintype "passive"))
      (node (ref "U1") (pin "8") (pinfunction "TXOP_8") (pintype "bidirectional"))
      (node (ref "U2") (pin "5") (pinfunction "TD+_5") (pintype "bidirectional"))
    )
    (net (code "82") (name "Net-(U1-XTLN)") (class "Default")
      (node (ref "C7") (pin "2") (pinfunction "2_2") (pintype "passive"))
      (node (ref "R11") (pin "2") (pinfunction "2_2") (pintype "passive"))
      (node (ref "U1") (pin "75") (pinfunction "XTLN_75") (pintype "bidirectional"))
      (node (ref "Y1") (pin "1") (pinfunction "1_1") (pintype "passive"))
    )
    (net (code "83") (name "Net-(U1-XTLP)") (class "Default")
      (node (ref "C6") (pin "2") (pinfunction "2_2") (pintype "passive"))
      (node (ref "R11") (pin "1") (pinfunction "1_1") (pintype "passive"))
      (node (ref "U1") (pin "76") (pinfunction "XTLP_76") (pintype "bidirectional"))
      (node (ref "Y1") (pin "2") (pinfunction "2_2") (pintype "passive"))
    )
    (net (code "84") (name "Net-(U2-GLED+)") (class "Default")
      (node (ref "R2") (pin "1") (pinfunction "1_1") (pintype "passive"))
      (node (ref "U2") (pin "13") (pinfunction "GLED+_13") (pintype "bidirectional"))
    )
    (net (code "85") (name "Net-(U2-YLED+)") (class "Default")
      (node (ref "R3") (pin "1") (pinfunction "1_1") (pintype "passive"))
      (node (ref "U2") (pin "11") (pinfunction "YLED+_11") (pintype "bidirectional"))
    )
    (net (code "86") (name "Net-(U3-LEFT)") (class "Default")
      (node (ref "R20") (pin "2") (pinfunction "2_2") (pintype "passive"))
      (node (ref "SJ3") (pin "1") (pinfunction "1_1") (pintype "passive"))
      (node (ref "U3") (pin "TIP") (pinfunction "LEFT_TIP") (pintype "bidirectional"))
    )
    (net (code "87") (name "VCC") (class "Default")
      (node (ref "C18") (pin "A") (pinfunction "+_A") (pintype "passive"))
      (node (ref "C19") (pin "1") (pinfunction "1_1") (pintype "passive"))
      (node (ref "D1") (pin "C") (pinfunction "C_C") (pintype "passive"))
      (node (ref "FDTI") (pin "4") (pinfunction "4_4") (pintype "passive"))
      (node (ref "IC2") (pin "3") (pinfunction "VO_3") (pintype "passive"))
      (node (ref "K1") (pin "1") (pinfunction "1_1") (pintype "passive"))
      (node (ref "POWER") (pin "4") (pinfunction "KL_4") (pintype "passive"))
      (node (ref "R12") (pin "2") (pinfunction "2_2") (pintype "passive"))
      (node (ref "R13") (pin "2") (pinfunction "2_2") (pintype "passive"))
      (node (ref "R14") (pin "2") (pinfunction "2_2") (pintype "passive"))
      (node (ref "R15") (pin "2") (pinfunction "2_2") (pintype "passive"))
      (node (ref "R17") (pin "1") (pinfunction "1_1") (pintype "passive"))
      (node (ref "R21") (pin "2") (pinfunction "2_2") (pintype "passive"))
      (node (ref "U$1") (pin "18") (pinfunction "AVCC_18") (pintype "bidirectional"))
      (node (ref "U$1") (pin "4") (pinfunction "VCC_4") (pintype "bidirectional"))
      (node (ref "U$1") (pin "6") (pinfunction "VCC_6") (pintype "bidirectional"))
    )
    (net (code "88") (name "unconnected-(IC3-OUT-Pad4)") (class "Default")
      (node (ref "IC3") (pin "4") (pinfunction "OUT_4") (pintype "output"))
    )
    (net (code "89") (name "unconnected-(U$1-ADC6-Pad19)") (class "Default")
      (node (ref "U$1") (pin "19") (pinfunction "ADC6_19") (pintype "bidirectional"))
    )
    (net (code "90") (name "unconnected-(U$1-ADC7-Pad22)") (class "Default")
      (node (ref "U$1") (pin "22") (pinfunction "ADC7_22") (pintype "bidirectional"))
    )
    (net (code "91") (name "unconnected-(U$2-A0-Pad1)") (class "Default")
      (node (ref "U$2") (pin "1") (pinfunction "A0_1") (pintype "bidirectional"))
    )
    (net (code "92") (name "unconnected-(U$2-A1-Pad2)") (class "Default")
      (node (ref "U$2") (pin "2") (pinfunction "A1_2") (pintype "bidirectional"))
    )
    (net (code "93") (name "unconnected-(U$2-WP-Pad7)") (class "Default")
      (node (ref "U$2") (pin "7") (pinfunction "WP_7") (pintype "bidirectional"))
    )
    (net (code "94") (name "unconnected-(U1-*INT-Pad56)") (class "Default")
      (node (ref "U1") (pin "56") (pinfunction "*INT_56") (pintype "bidirectional"))
    )
    (net (code "95") (name "unconnected-(U1-COLLED-Pad71)") (class "Default")
      (node (ref "U1") (pin "71") (pinfunction "COLLED_71") (pintype "bidirectional"))
    )
    (net (code "96") (name "unconnected-(U1-NC-Pad3)") (class "Default")
      (node (ref "U1") (pin "3") (pinfunction "NC_3") (pintype "bidirectional"))
    )
    (net (code "97") (name "unconnected-(U1-NC-Pad60)") (class "Default")
      (node (ref "U1") (pin "60") (pinfunction "NC_60") (pintype "bidirectional"))
    )
    (net (code "98") (name "unconnected-(U1-NC-Pad61)") (class "Default")
      (node (ref "U1") (pin "61") (pinfunction "NC_61") (pintype "bidirectional"))
    )
    (net (code "99") (name "unconnected-(U1-NC-Pad62)") (class "Default")
      (node (ref "U1") (pin "62") (pinfunction "NC_62") (pintype "bidirectional"))
    )
    (net (code "100") (name "unconnected-(U1-NC-Pad78)") (class "Default")
      (node (ref "U1") (pin "78") (pinfunction "NC_78") (pintype "bidirectional"))
    )
    (net (code "101") (name "unconnected-(U1-NC-Pad79)") (class "Default")
      (node (ref "U1") (pin "79") (pinfunction "NC_79") (pintype "bidirectional"))
    )
    (net (code "102") (name "unconnected-(U1-NC-Pad80)") (class "Default")
      (node (ref "U1") (pin "80") (pinfunction "NC_80") (pintype "bidirectional"))
    )
    (net (code "103") (name "unconnected-(U1-RXLED-Pad72)") (class "Default")
      (node (ref "U1") (pin "72") (pinfunction "RXLED_72") (pintype "bidirectional"))
    )
    (net (code "104") (name "unconnected-(U1-SPDLED-Pad67)") (class "Default")
      (node (ref "U1") (pin "67") (pinfunction "SPDLED_67") (pintype "bidirectional"))
    )
    (net (code "105") (name "unconnected-(U1-TXLED-Pad73)") (class "Default")
      (node (ref "U1") (pin "73") (pinfunction "TXLED_73") (pintype "bidirectional"))
    )
    (net (code "106") (name "unconnected-(U2-RCT-Pad3)") (class "Default")
      (node (ref "U2") (pin "3") (pinfunction "RCT_3") (pintype "bidirectional"))
    )
    (net (code "107") (name "unconnected-(U3-RIGHT-PadRING)") (class "Default")
      (node (ref "U3") (pin "RING") (pinfunction "RIGHT_RING") (pintype "bidirectional"))
    )
  )
)
